# input.net
KiCad netlist of a schematic drawn in EAGLE
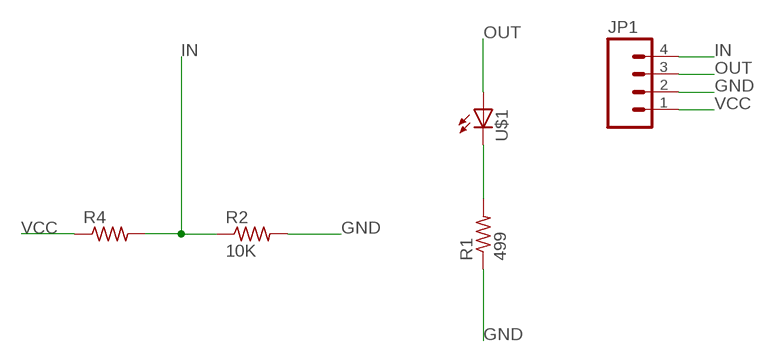
[diagram p0: schematic, sheet 1]

(export (version "E")
  (design (tool "Eeschema 10.0.6"))
  (components
    (comp (ref "JP1")
      (value "M04SMD")
      (footprint "eagle-import:1X04-SMD")
      (libsource (lib "eagle-import") (part "M04SMD"))
    )
    (comp (ref "R1")
      (value "499")
      (footprint "eagle-import:1206")
      (libsource (lib "eagle-import") (part "RESISTOR1206"))
    )
    (comp (ref "R2")
      (value "10K")
      (footprint "eagle-import:1206")
      (libsource (lib "eagle-import") (part "RESISTOR1206"))
    )
    (comp (ref "R4")
      (value "R-US_V526-0")
      (footprint "eagle-import:V526-0")
      (libsource (lib "eagle-import") (part "R-US_V526-0"))
    )
    (comp (ref "U$1")
      (value "LED1206")
      (footprint "eagle-import:1206")
      (libsource (lib "eagle-import") (part "LED1206"))
    )
  )
  (nets
    (net (code "1") (name "/GND") (class "Default")
      (node (ref "JP1") (pin "2") (pinfunction "2_2") (pintype "passive"))
      (node (ref "R1") (pin "1") (pinfunction "1_1") (pintype "passive"))
      (node (ref "R2") (pin "2") (pinfunction "2_2") (pintype "passive"))
    )
    (net (code "2") (name "/IN") (class "Default")
      (node (ref "JP1") (pin "4") (pinfunction "4_4") (pintype "passive"))
      (node (ref "R2") (pin "1") (pinfunction "1_1") (pintype "passive"))
      (node (ref "R4") (pin "2") (pinfunction "2_2") (pintype "passive"))
    )
    (net (code "3") (name "/OUT") (class "Default")
      (node (ref "JP1") (pin "3") (pinfunction "3_3") (pintype "passive"))
      (node (ref "U$1") (pin "1") (pinfunction "A_1") (pintype "passive"))
    )
    (net (code "4") (name "/VCC") (class "Default")
      (node (ref "JP1") (pin "1") (pinfunction "1_1") (pintype "passive"))
      (node (ref "R4") (pin "1") (pinfunction "1_1") (pintype "passive"))
    )
    (net (code "5") (name "Net-(U$1-C)") (class "Default")
      (node (ref "R1") (pin "2") (pinfunction "2_2") (pintype "passive"))
      (node (ref "U$1") (pin "2") (pinfunction "C_2") (pintype "passive"))
    )
  )
)
